# E9A_05_6231.net
KiCad netlist of a schematic drawn in Altium Designer
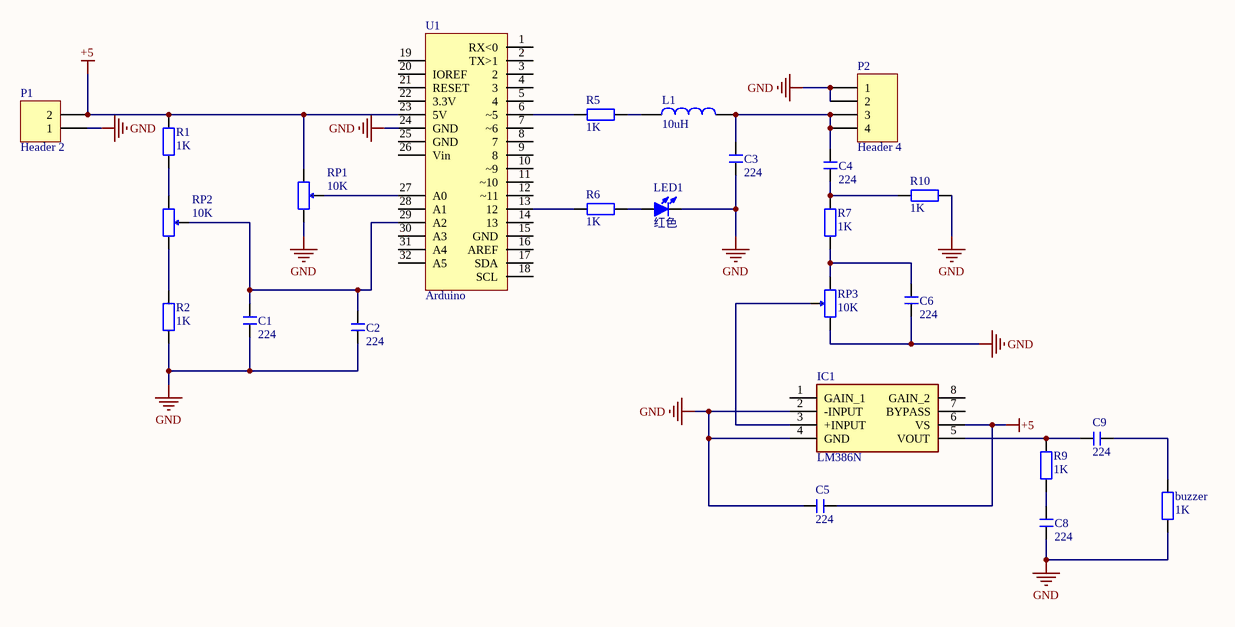
[diagram p0: E9A_05_6231.SchDoc]

(export (version "E")
  (design (tool "Eeschema 10.0.6"))
  (components
    (comp (ref "buzzer")
      (value "1K")
      (footprint "Buzzer")
      (description "直插色环电阻")
      (fields (field (name "版权归属") "源创客"))
      (libsource (lib "3.1   - 电阻-电容-电感") (part "R-CRR"))
    )
    (comp (ref "C1")
      (value "224")
      (footprint "MLCC5.08-A")
      (description "独石电容")
      (fields (field (name "版权归属") "源创客"))
      (libsource (lib "3.1   - 电阻-电容-电感") (part "C-MLCC"))
    )
    (comp (ref "C2")
      (value "224")
      (footprint "MLCC5.08-A")
      (description "独石电容")
      (fields (field (name "版权归属") "源创客"))
      (libsource (lib "3.1   - 电阻-电容-电感") (part "C-MLCC"))
    )
    (comp (ref "C3")
      (value "224")
      (footprint "MLCC5.08-A")
      (description "独石电容")
      (fields (field (name "版权归属") "源创客"))
      (libsource (lib "3.1   - 电阻-电容-电感") (part "C-MLCC"))
    )
    (comp (ref "C4")
      (value "224")
      (footprint "MLCC5.08-A")
      (description "独石电容")
      (fields (field (name "版权归属") "源创客"))
      (libsource (lib "3.1   - 电阻-电容-电感") (part "C-MLCC"))
    )
    (comp (ref "C5")
      (value "224")
      (footprint "MLCC5.08-A")
      (description "独石电容")
      (fields (field (name "版权归属") "源创客"))
      (libsource (lib "3.1   - 电阻-电容-电感") (part "C-MLCC"))
    )
    (comp (ref "C6")
      (value "224")
      (footprint "MLCC5.08-A")
      (description "独石电容")
      (fields (field (name "版权归属") "源创客"))
      (libsource (lib "3.1   - 电阻-电容-电感") (part "C-MLCC"))
    )
    (comp (ref "C8")
      (value "224")
      (footprint "MLCC5.08-A")
      (description "独石电容")
      (fields (field (name "版权归属") "源创客"))
      (libsource (lib "3.1   - 电阻-电容-电感") (part "C-MLCC"))
    )
    (comp (ref "C9")
      (value "224")
      (footprint "MLCC5.08-A")
      (description "独石电容")
      (fields (field (name "版权归属") "源创客"))
      (libsource (lib "3.1   - 电阻-电容-电感") (part "C-MLCC"))
    )
    (comp (ref "IC1")
      (value "LM386N")
      (footprint "SamacSys:DIP794W53P254L959H508Q8N")
      (description "Integrated Circuit")
      (fields (field (name "MOUSER PART NUMBER") "595-LM386N"))
      (libsource (lib "*") (part "LM386N"))
    )
    (comp (ref "L1")
      (value "10uH")
      (footprint "AL0307")
      (description "色环电感")
      (fields (field (name "版权归属") "源创客"))
      (libsource (lib "3.1   - 电阻-电容-电感") (part "L-AL"))
    )
    (comp (ref "LED1")
      (value "红色")
      (footprint "LED 3MM-B")
      (description "插件LED")
      (fields (field (name "版权归属") "源创客"))
      (libsource (lib "9.1   - LED") (part "LED-3MM"))
    )
    (comp (ref "P1")
      (value "Header 2")
      (footprint "POWER PLUG2")
      (description "Header, 2-Pin")
      (fields (field (name "PUBLISHER") "Altium Limited"))
      (libsource (lib "Miscellaneous Connectors") (part "Header 2"))
    )
    (comp (ref "P2")
      (value "Header 4")
      (footprint "HDR1X4")
      (description "Header, 4-Pin")
      (fields (field (name "PUBLISHER") "Altium Limited"))
      (libsource (lib "Miscellaneous Connectors") (part "Header 4"))
    )
    (comp (ref "R1")
      (value "1K")
      (footprint "RS 1/4W")
      (description "直插色环电阻")
      (fields (field (name "版权归属") "源创客"))
      (libsource (lib "3.1   - 电阻-电容-电感") (part "R-CRR"))
    )
    (comp (ref "R2")
      (value "1K")
      (footprint "RS 1/4W")
      (description "直插色环电阻")
      (fields (field (name "版权归属") "源创客"))
      (libsource (lib "3.1   - 电阻-电容-电感") (part "R-CRR"))
    )
    (comp (ref "R5")
      (value "1K")
      (footprint "RS 1/4W")
      (description "直插色环电阻")
      (fields (field (name "版权归属") "源创客"))
      (libsource (lib "3.1   - 电阻-电容-电感") (part "R-CRR"))
    )
    (comp (ref "R6")
      (value "1K")
      (footprint "RS 1/4W")
      (description "直插色环电阻")
      (fields (field (name "版权归属") "源创客"))
      (libsource (lib "3.1   - 电阻-电容-电感") (part "R-CRR"))
    )
    (comp (ref "R7")
      (value "1K")
      (footprint "RS 1/4W")
      (description "直插色环电阻")
      (fields (field (name "版权归属") "源创客"))
      (libsource (lib "3.1   - 电阻-电容-电感") (part "R-CRR"))
    )
    (comp (ref "R9")
      (value "1K")
      (footprint "RS 1/4W")
      (description "直插色环电阻")
      (fields (field (name "版权归属") "源创客"))
      (libsource (lib "3.1   - 电阻-电容-电感") (part "R-CRR"))
    )
    (comp (ref "R10")
      (value "1K")
      (footprint "RS 1/4W")
      (description "直插色环电阻")
      (fields (field (name "版权归属") "源创客"))
      (libsource (lib "3.1   - 电阻-电容-电感") (part "R-CRR"))
    )
    (comp (ref "RP1")
      (value "10K")
      (footprint "3266Y")
      (description "插件单联电位器")
      (fields (field (name "版权归属") "源创客"))
      (libsource (lib "3.1   - 电阻-电容-电感") (part "RP-ID"))
    )
    (comp (ref "RP2")
      (value "10K")
      (footprint "3266Y")
      (description "插件单联电位器")
      (fields (field (name "版权归属") "源创客"))
      (libsource (lib "3.1   - 电阻-电容-电感") (part "RP-ID"))
    )
    (comp (ref "RP3")
      (value "10K")
      (footprint "3266Y")
      (description "插件单联电位器")
      (fields (field (name "版权归属") "源创客"))
      (libsource (lib "3.1   - 电阻-电容-电感") (part "RP-ID"))
    )
    (comp (ref "U1")
      (value "Arduino")
      (footprint "Arduino-UNO")
      (libsource (lib "LixhSch") (part "Arduino-UNO"))
    )
  )
  (nets
    (net (code "1") (name "+5") (class "Default")
      (node (ref "C5") (pin "1") (pinfunction "1_1") (pintype "passive"))
      (node (ref "IC1") (pin "6") (pinfunction "VS_6") (pintype "passive"))
      (node (ref "P1") (pin "2") (pinfunction "2_2") (pintype "passive"))
      (node (ref "R1") (pin "2") (pinfunction "2_2") (pintype "passive"))
      (node (ref "RP1") (pin "1") (pinfunction "1_1") (pintype "passive"))
      (node (ref "U1") (pin "23") (pinfunction "5V_23") (pintype "power_in"))
    )
    (net (code "2") (name "GND") (class "Default")
      (node (ref "C1") (pin "1") (pinfunction "1_1") (pintype "passive"))
      (node (ref "C2") (pin "1") (pinfunction "1_1") (pintype "passive"))
      (node (ref "C3") (pin "1") (pinfunction "1_1") (pintype "passive"))
      (node (ref "C5") (pin "2") (pinfunction "2_2") (pintype "passive"))
      (node (ref "C6") (pin "1") (pinfunction "1_1") (pintype "passive"))
      (node (ref "C8") (pin "2") (pinfunction "2_2") (pintype "passive"))
      (node (ref "IC1") (pin "2") (pinfunction "-INPUT_2") (pintype "passive"))
      (node (ref "IC1") (pin "4") (pinfunction "GND_4") (pintype "passive"))
      (node (ref "LED1") (pin "2") (pinfunction "K_2") (pintype "passive"))
      (node (ref "P1") (pin "1") (pinfunction "1_1") (pintype "passive"))
      (node (ref "P2") (pin "1") (pinfunction "1_1") (pintype "passive"))
      (node (ref "P2") (pin "2") (pinfunction "2_2") (pintype "passive"))
      (node (ref "R10") (pin "2") (pinfunction "2_2") (pintype "passive"))
      (node (ref "R2") (pin "1") (pinfunction "1_1") (pintype "passive"))
      (node (ref "RP1") (pin "3") (pinfunction "3_3") (pintype "passive"))
      (node (ref "RP3") (pin "1") (pinfunction "1_1") (pintype "passive"))
      (node (ref "U1") (pin "24") (pinfunction "GND_24") (pintype "power_in"))
      (node (ref "buzzer") (pin "2") (pinfunction "2_2") (pintype "passive"))
    )
    (net (code "3") (name "Net-(C3-Pad2)") (class "Default")
      (node (ref "C3") (pin "2") (pinfunction "2_2") (pintype "passive"))
      (node (ref "C4") (pin "2") (pinfunction "2_2") (pintype "passive"))
      (node (ref "L1") (pin "2") (pinfunction "2_2") (pintype "passive"))
      (node (ref "P2") (pin "3") (pinfunction "3_3") (pintype "passive"))
      (node (ref "P2") (pin "4") (pinfunction "4_4") (pintype "passive"))
    )
    (net (code "4") (name "Net-(C4-Pad1)") (class "Default")
      (node (ref "C4") (pin "1") (pinfunction "1_1") (pintype "passive"))
      (node (ref "R10") (pin "1") (pinfunction "1_1") (pintype "passive"))
      (node (ref "R7") (pin "2") (pinfunction "2_2") (pintype "passive"))
    )
    (net (code "5") (name "Net-(C6-Pad2)") (class "Default")
      (node (ref "C6") (pin "2") (pinfunction "2_2") (pintype "passive"))
      (node (ref "R7") (pin "1") (pinfunction "1_1") (pintype "passive"))
      (node (ref "RP3") (pin "3") (pinfunction "3_3") (pintype "passive"))
    )
    (net (code "6") (name "Net-(C8-Pad1)") (class "Default")
      (node (ref "C8") (pin "1") (pinfunction "1_1") (pintype "passive"))
      (node (ref "R9") (pin "1") (pinfunction "1_1") (pintype "passive"))
    )
    (net (code "7") (name "Net-(C9-Pad1)") (class "Default")
      (node (ref "C9") (pin "1") (pinfunction "1_1") (pintype "passive"))
      (node (ref "buzzer") (pin "1") (pinfunction "1_1") (pintype "passive"))
    )
    (net (code "8") (name "Net-(IC1-+INPUT)") (class "Default")
      (node (ref "IC1") (pin "3") (pinfunction "+INPUT_3") (pintype "passive"))
      (node (ref "RP3") (pin "2") (pinfunction "2_2") (pintype "passive"))
    )
    (net (code "9") (name "Net-(IC1-VOUT)") (class "Default")
      (node (ref "C9") (pin "2") (pinfunction "2_2") (pintype "passive"))
      (node (ref "IC1") (pin "5") (pinfunction "VOUT_5") (pintype "passive"))
      (node (ref "R9") (pin "2") (pinfunction "2_2") (pintype "passive"))
    )
    (net (code "10") (name "Net-(L1-Pad1)") (class "Default")
      (node (ref "L1") (pin "1") (pinfunction "1_1") (pintype "passive"))
      (node (ref "R5") (pin "2") (pinfunction "2_2") (pintype "passive"))
    )
    (net (code "11") (name "Net-(LED1-A)") (class "Default")
      (node (ref "LED1") (pin "1") (pinfunction "A_1") (pintype "passive"))
      (node (ref "R6") (pin "2") (pinfunction "2_2") (pintype "passive"))
    )
    (net (code "12") (name "Net-(R1-Pad1)") (class "Default")
      (node (ref "R1") (pin "1") (pinfunction "1_1") (pintype "passive"))
      (node (ref "RP2") (pin "1") (pinfunction "1_1") (pintype "passive"))
    )
    (net (code "13") (name "Net-(R2-Pad2)") (class "Default")
      (node (ref "R2") (pin "2") (pinfunction "2_2") (pintype "passive"))
      (node (ref "RP2") (pin "3") (pinfunction "3_3") (pintype "passive"))
    )
    (net (code "14") (name "Net-(U1-12)") (class "Default")
      (node (ref "R6") (pin "1") (pinfunction "1_1") (pintype "passive"))
      (node (ref "U1") (pin "13") (pinfunction "12_13") (pintype "power_in"))
    )
    (net (code "15") (name "Net-(U1-A0)") (class "Default")
      (node (ref "RP1") (pin "2") (pinfunction "2_2") (pintype "passive"))
      (node (ref "U1") (pin "27") (pinfunction "A0_27") (pintype "power_in"))
    )
    (net (code "16") (name "Net-(U1-A2)") (class "Default")
      (node (ref "C1") (pin "2") (pinfunction "2_2") (pintype "passive"))
      (node (ref "C2") (pin "2") (pinfunction "2_2") (pintype "passive"))
      (node (ref "RP2") (pin "2") (pinfunction "2_2") (pintype "passive"))
      (node (ref "U1") (pin "29") (pinfunction "A2_29") (pintype "power_in"))
    )
    (net (code "17") (name "Net-(U1-~5)") (class "Default")
      (node (ref "R5") (pin "1") (pinfunction "1_1") (pintype "passive"))
      (node (ref "U1") (pin "6") (pinfunction "~5_6") (pintype "power_in"))
    )
    (net (code "18") (name "unconnected-(IC1-BYPASS-Pad7)") (class "Default")
      (node (ref "IC1") (pin "7") (pinfunction "BYPASS_7") (pintype "passive"))
    )
    (net (code "19") (name "unconnected-(IC1-GAIN_1-Pad1)") (class "Default")
      (node (ref "IC1") (pin "1") (pinfunction "GAIN_1_1") (pintype "passive"))
    )
    (net (code "20") (name "unconnected-(IC1-GAIN_2-Pad8)") (class "Default")
      (node (ref "IC1") (pin "8") (pinfunction "GAIN_2_8") (pintype "passive"))
    )
    (net (code "21") (name "unconnected-(U1-2-Pad3)") (class "Default")
      (node (ref "U1") (pin "3") (pinfunction "2_3") (pintype "power_in"))
    )
    (net (code "22") (name "unconnected-(U1-3-Pad4)") (class "Default")
      (node (ref "U1") (pin "4") (pinfunction "3_4") (pintype "power_in"))
    )
    (net (code "23") (name "unconnected-(U1-3.3V-Pad22)") (class "Default")
      (node (ref "U1") (pin "22") (pinfunction "3.3V_22") (pintype "power_in"))
    )
    (net (code "24") (name "unconnected-(U1-4-Pad5)") (class "Default")
      (node (ref "U1") (pin "5") (pinfunction "4_5") (pintype "power_in"))
    )
    (net (code "25") (name "unconnected-(U1-7-Pad8)") (class "Default")
      (node (ref "U1") (pin "8") (pinfunction "7_8") (pintype "power_in"))
    )
    (net (code "26") (name "unconnected-(U1-8-Pad9)") (class "Default")
      (node (ref "U1") (pin "9") (pinfunction "8_9") (pintype "power_in"))
    )
    (net (code "27") (name "unconnected-(U1-13-Pad14)") (class "Default")
      (node (ref "U1") (pin "14") (pinfunction "13_14") (pintype "power_in"))
    )
    (net (code "28") (name "unconnected-(U1-A1-Pad28)") (class "Default")
      (node (ref "U1") (pin "28") (pinfunction "A1_28") (pintype "power_in"))
    )
    (net (code "29") (name "unconnected-(U1-A3-Pad30)") (class "Default")
      (node (ref "U1") (pin "30") (pinfunction "A3_30") (pintype "power_in"))
    )
    (net (code "30") (name "unconnected-(U1-A4-Pad31)") (class "Default")
      (node (ref "U1") (pin "31") (pinfunction "A4_31") (pintype "power_in"))
    )
    (net (code "31") (name "unconnected-(U1-A5-Pad32)") (class "Default")
      (node (ref "U1") (pin "32") (pinfunction "A5_32") (pintype "power_in"))
    )
    (net (code "32") (name "unconnected-(U1-AREF-Pad16)") (class "Default")
      (node (ref "U1") (pin "16") (pinfunction "AREF_16") (pintype "power_in"))
    )
    (net (code "33") (name "unconnected-(U1-GND-Pad15)") (class "Default")
      (node (ref "U1") (pin "15") (pinfunction "GND_15") (pintype "power_in"))
    )
    (net (code "34") (name "unconnected-(U1-GND-Pad25)") (class "Default")
      (node (ref "U1") (pin "25") (pinfunction "GND_25") (pintype "power_in"))
    )
    (net (code "35") (name "unconnected-(U1-IOREF-Pad20)") (class "Default")
      (node (ref "U1") (pin "20") (pinfunction "IOREF_20") (pintype "power_in"))
    )
    (net (code "36") (name "unconnected-(U1-Pad19)") (class "Default")
      (node (ref "U1") (pin "19") (pintype "power_in"))
    )
    (net (code "37") (name "unconnected-(U1-RESET-Pad21)") (class "Default")
      (node (ref "U1") (pin "21") (pinfunction "RESET_21") (pintype "power_in"))
    )
    (net (code "38") (name "unconnected-(U1-RX<0-Pad1)") (class "Default")
      (node (ref "U1") (pin "1") (pinfunction "RX<0_1") (pintype "power_in"))
    )
    (net (code "39") (name "unconnected-(U1-SCL-Pad18)") (class "Default")
      (node (ref "U1") (pin "18") (pinfunction "SCL_18") (pintype "power_in"))
    )
    (net (code "40") (name "unconnected-(U1-SDA-Pad17)") (class "Default")
      (node (ref "U1") (pin "17") (pinfunction "SDA_17") (pintype "power_in"))
    )
    (net (code "41") (name "unconnected-(U1-TX>1-Pad2)") (class "Default")
      (node (ref "U1") (pin "2") (pinfunction "TX>1_2") (pintype "power_in"))
    )
    (net (code "42") (name "unconnected-(U1-Vin-Pad26)") (class "Default")
      (node (ref "U1") (pin "26") (pinfunction "Vin_26") (pintype "power_in"))
    )
    (net (code "43") (name "unconnected-(U1-~6-Pad7)") (class "Default")
      (node (ref "U1") (pin "7") (pinfunction "~6_7") (pintype "power_in"))
    )
    (net (code "44") (name "unconnected-(U1-~9-Pad10)") (class "Default")
      (node (ref "U1") (pin "10") (pinfunction "~9_10") (pintype "power_in"))
    )
    (net (code "45") (name "unconnected-(U1-~10-Pad11)") (class "Default")
      (node (ref "U1") (pin "11") (pinfunction "~10_11") (pintype "power_in"))
    )
    (net (code "46") (name "unconnected-(U1-~11-Pad12)") (class "Default")
      (node (ref "U1") (pin "12") (pinfunction "~11_12") (pintype "power_in"))
    )
  )
)
